# Clock1_3.net
KiCad netlist of a schematic drawn in EAGLE
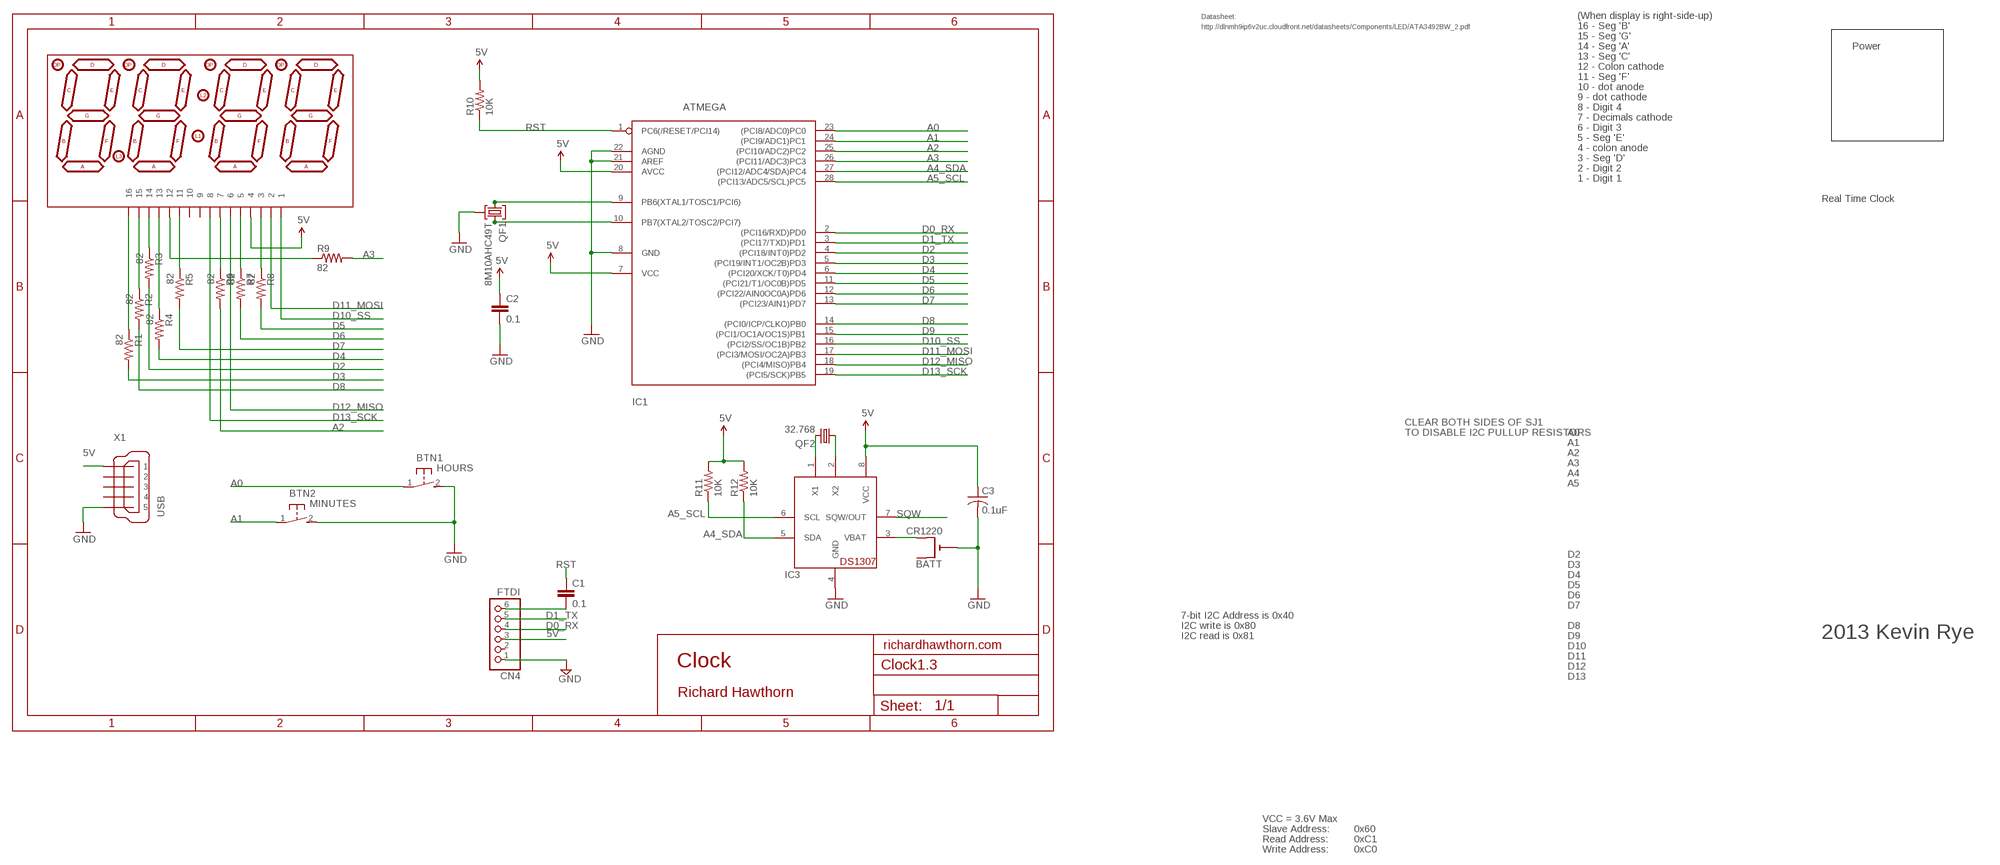
[diagram p0: schematic, sheet 1]

(export (version "E")
  (design (tool "Eeschema 10.0.6"))
  (components
    (comp (ref "BATT")
      (value "CR1220")
      (footprint "eagle-import:CR1220-SMD")
      (libsource (lib "eagle-import") (part "CR1220SMT"))
    )
    (comp (ref "BTN1")
      (value "HOURS")
      (footprint "eagle-import:DTS-3")
      (libsource (lib "eagle-import") (part "DTS-3"))
    )
    (comp (ref "BTN2")
      (value "MINUTES")
      (footprint "eagle-import:DTS-3")
      (libsource (lib "eagle-import") (part "DTS-3"))
    )
    (comp (ref "C1")
      (value "0.1")
      (footprint "eagle-import:CAP-PTH-SMALL2")
      (libsource (lib "eagle-import") (part "CAPPTH2"))
    )
    (comp (ref "C2")
      (value "0.1")
      (footprint "eagle-import:CAP-PTH-SMALL2")
      (libsource (lib "eagle-import") (part "CAPPTH2"))
    )
    (comp (ref "C3")
      (value "0.1uF")
      (footprint "eagle-import:C025-025X050")
      (libsource (lib "eagle-import") (part "C-US025-025X050"))
    )
    (comp (ref "CN4")
      (value "FTDI")
      (footprint "eagle-import:1X06")
      (libsource (lib "eagle-import") (part "PINHD-1X6"))
    )
    (comp (ref "IC1")
      (value "ATMEGA")
      (footprint "eagle-import:DIL28-3-ROUND")
      (libsource (lib "eagle-import") (part "ATMEGA168PROUND"))
    )
    (comp (ref "IC3")
      (value "DS1307")
      (footprint "eagle-import:DIL08")
      (libsource (lib "eagle-import") (part "DS1307"))
    )
    (comp (ref "LED1")
      (value "7SEG-4DIGIT")
      (footprint "eagle-import:SPARKFUN_7-SEGMENT-4DIGIT")
      (libsource (lib "eagle-import") (part "7SEG-4DIGIT"))
    )
    (comp (ref "QF1")
      (value "8M10AHC49T")
      (footprint "eagle-import:HC49U")
      (libsource (lib "eagle-import") (part "8M10AHC49T"))
    )
    (comp (ref "QF2")
      (value "32.768")
      (footprint "eagle-import:TC38H")
      (libsource (lib "eagle-import") (part "CRYTALTC38H"))
    )
    (comp (ref "R1")
      (value "82")
      (footprint "eagle-import:0204_7")
      (libsource (lib "eagle-import") (part "R-US_0204/7"))
    )
    (comp (ref "R2")
      (value "82")
      (footprint "eagle-import:0204_7")
      (libsource (lib "eagle-import") (part "R-US_0204/7"))
    )
    (comp (ref "R3")
      (value "82")
      (footprint "eagle-import:0204_7")
      (libsource (lib "eagle-import") (part "R-US_0204/7"))
    )
    (comp (ref "R4")
      (value "82")
      (footprint "eagle-import:0204_7")
      (libsource (lib "eagle-import") (part "R-US_0204/7"))
    )
    (comp (ref "R5")
      (value "82")
      (footprint "eagle-import:0204_7")
      (libsource (lib "eagle-import") (part "R-US_0204/7"))
    )
    (comp (ref "R6")
      (value "82")
      (footprint "eagle-import:0204_7")
      (libsource (lib "eagle-import") (part "R-US_0204/7"))
    )
    (comp (ref "R7")
      (value "82")
      (footprint "eagle-import:0204_7")
      (libsource (lib "eagle-import") (part "R-US_0204/7"))
    )
    (comp (ref "R8")
      (value "82")
      (footprint "eagle-import:0204_7")
      (libsource (lib "eagle-import") (part "R-US_0204/7"))
    )
    (comp (ref "R9")
      (value "82")
      (footprint "eagle-import:0204_7")
      (libsource (lib "eagle-import") (part "R-US_0204/7"))
    )
    (comp (ref "R10")
      (value "10K")
      (footprint "eagle-import:0204_7")
      (libsource (lib "eagle-import") (part "R-US_0204/7"))
    )
    (comp (ref "R11")
      (value "10K")
      (footprint "eagle-import:0204_7")
      (libsource (lib "eagle-import") (part "R-US_0204/7"))
    )
    (comp (ref "R12")
      (value "10K")
      (footprint "eagle-import:0204_7")
      (libsource (lib "eagle-import") (part "R-US_0204/7"))
    )
    (comp (ref "X1")
      (value "USB")
      (footprint "eagle-import:32005-601")
      (libsource (lib "eagle-import") (part "MINI-USB_SHIELD5P2-32005-601"))
    )
  )
  (nets
    (net (code "1") (name "/A0") (class "Default")
      (node (ref "BTN1") (pin "1") (pinfunction "1_1") (pintype "passive"))
      (node (ref "IC1") (pin "23") (pinfunction "(PCI8/ADC0)PC0_23") (pintype "bidirectional"))
    )
    (net (code "2") (name "/A1") (class "Default")
      (node (ref "BTN2") (pin "1") (pinfunction "1_1") (pintype "passive"))
      (node (ref "IC1") (pin "24") (pinfunction "(PCI9/ADC1)PC1_24") (pintype "bidirectional"))
    )
    (net (code "3") (name "/A2") (class "Default")
      (node (ref "IC1") (pin "25") (pinfunction "(PCI10/ADC2)PC2_25") (pintype "bidirectional"))
      (node (ref "R6") (pin "2") (pinfunction "2_2") (pintype "passive"))
    )
    (net (code "4") (name "/A3") (class "Default")
      (node (ref "IC1") (pin "26") (pinfunction "(PCI11/ADC3)PC3_26") (pintype "bidirectional"))
      (node (ref "R9") (pin "2") (pinfunction "2_2") (pintype "passive"))
    )
    (net (code "5") (name "/A4_SDA") (class "Default")
      (node (ref "IC1") (pin "27") (pinfunction "(PCI12/ADC4/SDA)PC4_27") (pintype "bidirectional"))
      (node (ref "IC3") (pin "5") (pinfunction "SDA_5") (pintype "bidirectional"))
      (node (ref "R12") (pin "1") (pinfunction "1_1") (pintype "passive"))
    )
    (net (code "6") (name "/A5_SCL") (class "Default")
      (node (ref "IC1") (pin "28") (pinfunction "(PCI13/ADC5/SCL)PC5_28") (pintype "bidirectional"))
      (node (ref "IC3") (pin "6") (pinfunction "SCL_6") (pintype "bidirectional"))
      (node (ref "R11") (pin "1") (pinfunction "1_1") (pintype "passive"))
    )
    (net (code "7") (name "/D0_RX") (class "Default")
      (node (ref "CN4") (pin "4") (pinfunction "4_4") (pintype "passive"))
      (node (ref "IC1") (pin "2") (pinfunction "(PCI16/RXD)PD0_2") (pintype "bidirectional"))
    )
    (net (code "8") (name "/D1_TX") (class "Default")
      (node (ref "CN4") (pin "5") (pinfunction "5_5") (pintype "passive"))
      (node (ref "IC1") (pin "3") (pinfunction "(PCI17/TXD)PD1_3") (pintype "bidirectional"))
    )
    (net (code "9") (name "/D2") (class "Default")
      (node (ref "IC1") (pin "4") (pinfunction "(PCI18/INT0)PD2_4") (pintype "bidirectional"))
      (node (ref "R3") (pin "2") (pinfunction "2_2") (pintype "passive"))
    )
    (net (code "10") (name "/D3") (class "Default")
      (node (ref "IC1") (pin "5") (pinfunction "(PCI19/INT1/OC2B)PD3_5") (pintype "bidirectional"))
      (node (ref "R1") (pin "2") (pinfunction "2_2") (pintype "passive"))
    )
    (net (code "11") (name "/D4") (class "Default")
      (node (ref "IC1") (pin "6") (pinfunction "(PCI20/XCK/T0)PD4_6") (pintype "bidirectional"))
      (node (ref "R4") (pin "2") (pinfunction "2_2") (pintype "passive"))
    )
    (net (code "12") (name "/D5") (class "Default")
      (node (ref "IC1") (pin "11") (pinfunction "(PCI21/T1/OC0B)PD5_11") (pintype "bidirectional"))
      (node (ref "R8") (pin "2") (pinfunction "2_2") (pintype "passive"))
    )
    (net (code "13") (name "/D6") (class "Default")
      (node (ref "IC1") (pin "12") (pinfunction "(PCI22/AIN0OC0A)PD6_12") (pintype "bidirectional"))
      (node (ref "R7") (pin "2") (pinfunction "2_2") (pintype "passive"))
    )
    (net (code "14") (name "/D7") (class "Default")
      (node (ref "IC1") (pin "13") (pinfunction "(PCI23/AIN1)PD7_13") (pintype "bidirectional"))
      (node (ref "R5") (pin "2") (pinfunction "2_2") (pintype "passive"))
    )
    (net (code "15") (name "/D8") (class "Default")
      (node (ref "IC1") (pin "14") (pinfunction "(PCI0/ICP/CLKO)PB0_14") (pintype "bidirectional"))
      (node (ref "R2") (pin "2") (pinfunction "2_2") (pintype "passive"))
    )
    (net (code "16") (name "/D9") (class "Default")
      (node (ref "IC1") (pin "15") (pinfunction "(PCI1/OC1A/OC1S)PB1_15") (pintype "bidirectional"))
    )
    (net (code "17") (name "/D10_SS") (class "Default")
      (node (ref "IC1") (pin "16") (pinfunction "(PCI2/SS/OC1B)PB2_16") (pintype "bidirectional"))
      (node (ref "LED1") (pin "1") (pinfunction "1_1") (pintype "bidirectional"))
    )
    (net (code "18") (name "/D11_MOSI") (class "Default")
      (node (ref "IC1") (pin "17") (pinfunction "(PCI3/MOSI/OC2A)PB3_17") (pintype "bidirectional"))
      (node (ref "LED1") (pin "2") (pinfunction "2_2") (pintype "bidirectional"))
    )
    (net (code "19") (name "/D12_MISO") (class "Default")
      (node (ref "IC1") (pin "18") (pinfunction "(PCI4/MISO)PB4_18") (pintype "bidirectional"))
      (node (ref "LED1") (pin "6") (pinfunction "6_6") (pintype "bidirectional"))
    )
    (net (code "20") (name "/D13_SCK") (class "Default")
      (node (ref "IC1") (pin "19") (pinfunction "(PCI5/SCK)PB5_19") (pintype "bidirectional"))
      (node (ref "LED1") (pin "8") (pinfunction "8_8") (pintype "bidirectional"))
    )
    (net (code "21") (name "/RST") (class "Default")
      (node (ref "C1") (pin "1") (pinfunction "1_1") (pintype "passive"))
      (node (ref "IC1") (pin "1") (pinfunction "PC6(/RESET/PCI14)_1") (pintype "bidirectional"))
      (node (ref "R10") (pin "1") (pinfunction "1_1") (pintype "passive"))
    )
    (net (code "22") (name "/SQW") (class "Default")
      (node (ref "IC3") (pin "7") (pinfunction "SQW/OUT_7") (pintype "bidirectional"))
    )
    (net (code "23") (name "5V") (class "Default")
      (node (ref "C2") (pin "1") (pinfunction "1_1") (pintype "passive"))
      (node (ref "C3") (pin "1") (pinfunction "1_1") (pintype "passive"))
      (node (ref "CN4") (pin "3") (pinfunction "3_3") (pintype "passive"))
      (node (ref "IC1") (pin "20") (pinfunction "AVCC_20") (pintype "bidirectional"))
      (node (ref "IC1") (pin "7") (pinfunction "VCC_7") (pintype "bidirectional"))
      (node (ref "IC3") (pin "8") (pinfunction "VCC_8") (pintype "power_in"))
      (node (ref "LED1") (pin "4") (pinfunction "4_4") (pintype "bidirectional"))
      (node (ref "R10") (pin "2") (pinfunction "2_2") (pintype "passive"))
      (node (ref "R11") (pin "2") (pinfunction "2_2") (pintype "passive"))
      (node (ref "R12") (pin "2") (pinfunction "2_2") (pintype "passive"))
      (node (ref "X1") (pin "1") (pinfunction "1_1") (pintype "passive"))
    )
    (net (code "24") (name "GND") (class "Default")
      (node (ref "BATT") (pin "-") (pinfunction "-_-") (pintype "passive"))
      (node (ref "BTN1") (pin "2") (pinfunction "2_2") (pintype "passive"))
      (node (ref "BTN2") (pin "2") (pinfunction "2_2") (pintype "passive"))
      (node (ref "C2") (pin "2") (pinfunction "2_2") (pintype "passive"))
      (node (ref "C3") (pin "2") (pinfunction "2_2") (pintype "passive"))
      (node (ref "CN4") (pin "1") (pinfunction "1_1") (pintype "passive"))
      (node (ref "IC1") (pin "21") (pinfunction "AREF_21") (pintype "bidirectional"))
      (node (ref "IC1") (pin "22") (pinfunction "AGND_22") (pintype "bidirectional"))
      (node (ref "IC1") (pin "8") (pinfunction "GND_8") (pintype "bidirectional"))
      (node (ref "IC3") (pin "4") (pinfunction "GND_4") (pintype "power_in"))
      (node (ref "QF1") (pin "2") (pinfunction "2_2") (pintype "passive"))
      (node (ref "X1") (pin "5") (pinfunction "5_5") (pintype "passive"))
    )
    (net (code "25") (name "Net-(BATT-+1)") (class "Default")
      (node (ref "BATT") (pin "+$2") (pinfunction "+1_+$2") (pintype "passive"))
      (node (ref "IC3") (pin "3") (pinfunction "VBAT_3") (pintype "power_in"))
    )
    (net (code "26") (name "Net-(C1-Pad2)") (class "Default")
      (node (ref "C1") (pin "2") (pinfunction "2_2") (pintype "passive"))
      (node (ref "CN4") (pin "6") (pinfunction "6_6") (pintype "passive"))
    )
    (net (code "27") (name "Net-(IC1-PB6(XTAL1{slash}TOSC1{slash}PCI6))") (class "Default")
      (node (ref "IC1") (pin "9") (pinfunction "PB6(XTAL1/TOSC1/PCI6)_9") (pintype "bidirectional"))
      (node (ref "QF1") (pin "1") (pinfunction "1_1") (pintype "passive"))
    )
    (net (code "28") (name "Net-(IC1-PB7(XTAL2{slash}TOSC2{slash}PCI7))") (class "Default")
      (node (ref "IC1") (pin "10") (pinfunction "PB7(XTAL2/TOSC2/PCI7)_10") (pintype "bidirectional"))
      (node (ref "QF1") (pin "3") (pinfunction "3_3") (pintype "passive"))
    )
    (net (code "29") (name "Net-(IC3-X1)") (class "Default")
      (node (ref "IC3") (pin "1") (pinfunction "X1_1") (pintype "passive"))
      (node (ref "QF2") (pin "2") (pinfunction "2_2") (pintype "passive"))
    )
    (net (code "30") (name "Net-(IC3-X2)") (class "Default")
      (node (ref "IC3") (pin "2") (pinfunction "X2_2") (pintype "passive"))
      (node (ref "QF2") (pin "1") (pinfunction "1_1") (pintype "passive"))
    )
    (net (code "31") (name "Net-(LED1-Pad3)") (class "Default")
      (node (ref "LED1") (pin "3") (pinfunction "3_3") (pintype "bidirectional"))
      (node (ref "R8") (pin "1") (pinfunction "1_1") (pintype "passive"))
    )
    (net (code "32") (name "Net-(LED1-Pad5)") (class "Default")
      (node (ref "LED1") (pin "5") (pinfunction "5_5") (pintype "bidirectional"))
      (node (ref "R7") (pin "1") (pinfunction "1_1") (pintype "passive"))
    )
    (net (code "33") (name "Net-(LED1-Pad7)") (class "Default")
      (node (ref "LED1") (pin "7") (pinfunction "7_7") (pintype "bidirectional"))
      (node (ref "R6") (pin "1") (pinfunction "1_1") (pintype "passive"))
    )
    (net (code "34") (name "Net-(LED1-Pad11)") (class "Default")
      (node (ref "LED1") (pin "11") (pinfunction "11_11") (pintype "bidirectional"))
      (node (ref "R5") (pin "1") (pinfunction "1_1") (pintype "passive"))
    )
    (net (code "35") (name "Net-(LED1-Pad12)") (class "Default")
      (node (ref "LED1") (pin "12") (pinfunction "12_12") (pintype "bidirectional"))
      (node (ref "R9") (pin "1") (pinfunction "1_1") (pintype "passive"))
    )
    (net (code "36") (name "Net-(LED1-Pad13)") (class "Default")
      (node (ref "LED1") (pin "13") (pinfunction "13_13") (pintype "bidirectional"))
      (node (ref "R4") (pin "1") (pinfunction "1_1") (pintype "passive"))
    )
    (net (code "37") (name "Net-(LED1-Pad14)") (class "Default")
      (node (ref "LED1") (pin "14") (pinfunction "14_14") (pintype "bidirectional"))
      (node (ref "R3") (pin "1") (pinfunction "1_1") (pintype "passive"))
    )
    (net (code "38") (name "Net-(LED1-Pad15)") (class "Default")
      (node (ref "LED1") (pin "15") (pinfunction "15_15") (pintype "bidirectional"))
      (node (ref "R2") (pin "1") (pinfunction "1_1") (pintype "passive"))
    )
    (net (code "39") (name "Net-(LED1-Pad16)") (class "Default")
      (node (ref "LED1") (pin "16") (pinfunction "16_16") (pintype "bidirectional"))
      (node (ref "R1") (pin "1") (pinfunction "1_1") (pintype "passive"))
    )
    (net (code "40") (name "unconnected-(BATT-+-Pad+$1)") (class "Default")
      (node (ref "BATT") (pin "+$1") (pinfunction "+_+$1") (pintype "passive"))
    )
    (net (code "41") (name "unconnected-(CN4-Pad2)") (class "Default")
      (node (ref "CN4") (pin "2") (pinfunction "2_2") (pintype "passive"))
    )
    (net (code "42") (name "unconnected-(LED1-Pad9)") (class "Default")
      (node (ref "LED1") (pin "9") (pinfunction "9_9") (pintype "bidirectional"))
    )
    (net (code "43") (name "unconnected-(LED1-Pad10)") (class "Default")
      (node (ref "LED1") (pin "10") (pinfunction "10_10") (pintype "bidirectional"))
    )
    (net (code "44") (name "unconnected-(X1-Pad2)") (class "Default")
      (node (ref "X1") (pin "2") (pinfunction "2_2") (pintype "passive"))
    )
    (net (code "45") (name "unconnected-(X1-Pad3)") (class "Default")
      (node (ref "X1") (pin "3") (pinfunction "3_3") (pintype "passive"))
    )
    (net (code "46") (name "unconnected-(X1-Pad4)") (class "Default")
      (node (ref "X1") (pin "4") (pinfunction "4_4") (pintype "passive"))
    )
  )
)
